# Battery.net
KiCad netlist of a schematic drawn in Altium Designer
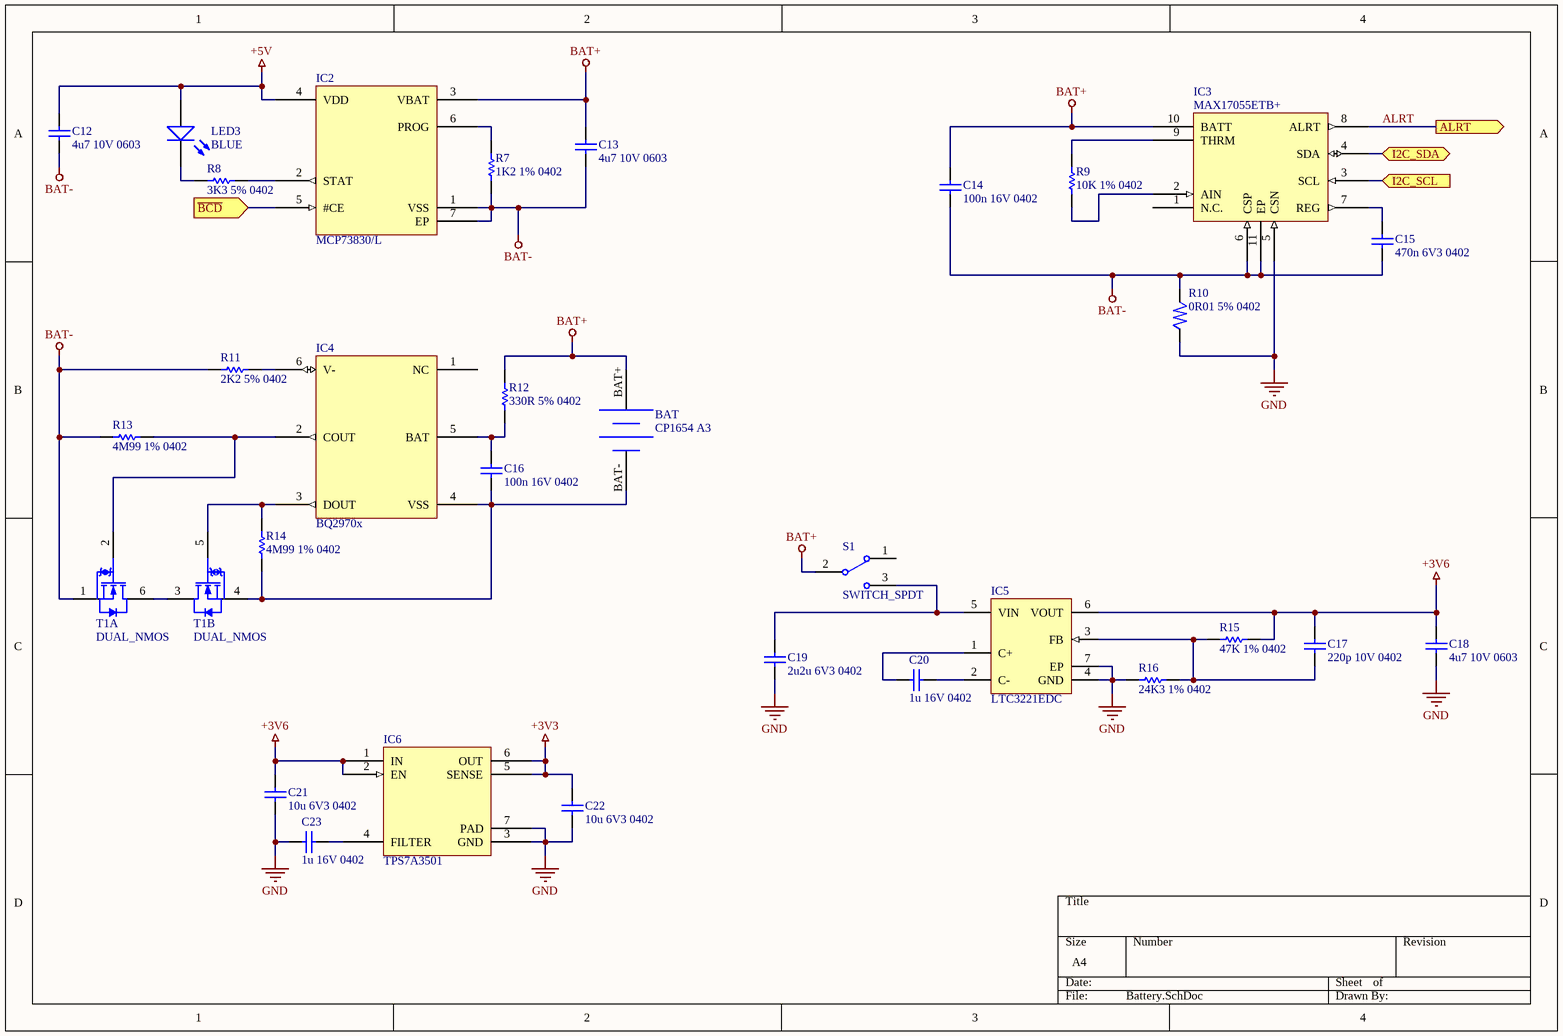
[diagram p0: Battery.SchDoc]

(export (version "E")
  (design (tool "Eeschema 10.0.6"))
  (components
    (comp (ref "BAT")
      (value "CP1654 A3")
      (footprint "CP1654")
      (libsource (lib "bleimuv6_intlib") (part "Battery"))
    )
    (comp (ref "C12")
      (value "4u7 10V 0603")
      (footprint "CAPC0603(1608)100_L")
      (description "CAP 4.7uF 10V ±20% 0603 (1608 Metric) Thickness 1mm SMD")
      (fields (field (name "TOLERANCE") "Â±20%"))
      (libsource (lib "Altium Content Vault") (part "CAP"))
    )
    (comp (ref "C13")
      (value "4u7 10V 0603")
      (footprint "CAPC0603(1608)100_L")
      (description "CAP 4.7uF 10V ±20% 0603 (1608 Metric) Thickness 1mm SMD")
      (fields (field (name "TOLERANCE") "Â±20%"))
      (libsource (lib "Altium Content Vault") (part "CAP"))
    )
    (comp (ref "C14")
      (value "100n 16V 0402")
      (footprint "CAPC0402(1005)60_L")
      (description "CAP 100nF 16V ±10% 0402 (1005 Metric) Thickness 0.6mm SMD")
      (fields (field (name "TOLERANCE") "Â±10%"))
      (libsource (lib "Altium Content Vault") (part "CAP"))
    )
    (comp (ref "C15")
      (value "470n 6V3 0402")
      (footprint "CAPC0402(1005)60_L")
      (description "CAP 470nF 6.3V ±10% 0402 (1005 Metric) Thickness 0.6mm SMD")
      (fields (field (name "TOLERANCE") "Â±10%"))
      (libsource (lib "Altium Content Vault") (part "CAP"))
    )
    (comp (ref "C16")
      (value "100n 16V 0402")
      (footprint "CAPC0402(1005)60_L")
      (description "CAP 100nF 16V ±10% 0402 (1005 Metric) Thickness 0.6mm SMD")
      (fields (field (name "TOLERANCE") "Â±10%"))
      (libsource (lib "Altium Content Vault") (part "CAP"))
    )
    (comp (ref "C17")
      (value "220p 10V 0402")
      (footprint "CAPC0402(1005)60_L")
      (description "CAP 220pF 10V ±5% 0402 (1005 Metric) Thickness 0.6mm SMD")
      (fields (field (name "TOLERANCE") "Â±5%"))
      (libsource (lib "Altium Content Vault") (part "CAP"))
    )
    (comp (ref "C18")
      (value "4u7 10V 0603")
      (footprint "CAPC0603(1608)100_L")
      (description "CAP 4.7uF 10V ±20% 0603 (1608 Metric) Thickness 1mm SMD")
      (fields (field (name "TOLERANCE") "Â±20%"))
      (libsource (lib "Altium Content Vault") (part "CAP"))
    )
    (comp (ref "C19")
      (value "2u2u 6V3 0402")
      (footprint "CAPC0402(1005)60_L")
      (description "CAP 2.2uF 6.3V ±10% 0402 (1005 Metric) Thickness 0.6mm SMD")
      (fields (field (name "TOLERANCE") "Â±10%"))
      (libsource (lib "Altium Content Vault") (part "CAP"))
    )
    (comp (ref "C20")
      (value "1u 16V 0402")
      (footprint "CAPC0402(1005)60_L")
      (description "CAP 1uF 16V ±10% 0402 (1005 Metric) Thickness 0.6mm SMD")
      (fields (field (name "TOLERANCE") "Â±10%"))
      (libsource (lib "Altium Content Vault") (part "CAP"))
    )
    (comp (ref "C21")
      (value "10u 6V3 0402")
      (footprint "CAPC0402(1005)60_L")
      (description "CAP 10uF 6.3V ±20% 0402 (1005 Metric) Thickness 0.6mm SMD")
      (fields (field (name "TOLERANCE") "Â±20%"))
      (libsource (lib "Altium Content Vault") (part "CAP"))
    )
    (comp (ref "C22")
      (value "10u 6V3 0402")
      (footprint "CAPC0402(1005)60_L")
      (description "CAP 10uF 6.3V ±20% 0402 (1005 Metric) Thickness 0.6mm SMD")
      (fields (field (name "TOLERANCE") "Â±20%"))
      (libsource (lib "Altium Content Vault") (part "CAP"))
    )
    (comp (ref "C23")
      (value "1u 16V 0402")
      (footprint "CAPC0402(1005)60_L")
      (description "CAP 1uF 16V ±10% 0402 (1005 Metric) Thickness 0.6mm SMD")
      (fields (field (name "TOLERANCE") "Â±10%"))
      (libsource (lib "Altium Content Vault") (part "CAP"))
    )
    (comp (ref "IC2")
      (value "MCP73830/L")
      (footprint "PSON50P200X80_HS-7L")
      (libsource (lib "bleimuv6_intlib") (part "MCP73830/L"))
    )
    (comp (ref "IC3")
      (value "MAX17055ETB+")
      (footprint "PSON40P250X80_HS-11L")
      (libsource (lib "bleimuv6_intlib") (part "MAX17055ETB+"))
    )
    (comp (ref "IC4")
      (value "BQ2970x")
      (footprint "SON50P150X80-6L")
      (libsource (lib "bleimuv6_intlib") (part "BQ2970x"))
    )
    (comp (ref "IC5")
      (value "LTC3221EDC")
      (footprint "LT-DC6-6_V")
      (fields (field (name "MANUFACTURER") "Linear Technology"))
      (libsource (lib "Altium Content Vault") (part "LT-LTC3221-DC6-6_B"))
    )
    (comp (ref "IC6")
      (value "TPS7A3501")
      (footprint "PSON65P200X80_HS-7L")
      (libsource (lib "bleimuv6_intlib") (part "TPS7A3501"))
    )
    (comp (ref "LED3")
      (value "BLUE")
      (footprint "LED_0402")
      (description "Generic 0402 LED")
      (libsource (lib "bleimuv6_schlib") (part "LED"))
    )
    (comp (ref "R7")
      (value "1K2 1% 0402")
      (footprint "RESC0402(1005)_L")
      (description "1K2 0.063W 1% 0402 (1005 Metric)  SMD")
      (fields (field (name "POWER") "0.063 W") (field (name "TOLERANCE") "1 %"))
      (libsource (lib "Altium Content Vault") (part "RES"))
    )
    (comp (ref "R8")
      (value "3K3 5% 0402")
      (footprint "RESC0402(1005)_L")
      (description "3K3 0.063W 5% 0402 (1005 Metric)  SMD")
      (fields (field (name "POWER") "0.063 W") (field (name "TOLERANCE") "5 %"))
      (libsource (lib "Altium Content Vault") (part "RES"))
    )
    (comp (ref "R9")
      (value "10K 1% 0402")
      (footprint "RESC0402(1005)_L")
      (description "10K 0.063W 1% 0402 (1005 Metric)  SMD")
      (fields (field (name "TOLERANCE") "1 %") (field (name "POWER") "0.063 W"))
      (libsource (lib "Altium Content Vault") (part "RES"))
    )
    (comp (ref "R10")
      (value "0R01 5% 0402")
      (footprint "R0402")
      (libsource (lib "bleimuv6_intlib") (part "Resistor"))
    )
    (comp (ref "R11")
      (value "2K2 5% 0402")
      (footprint "RESC0402(1005)_L")
      (description "2K2 0.063W 5% 0402 (1005 Metric)  SMD")
      (fields (field (name "TOLERANCE") "5 %") (field (name "POWER") "0.063 W"))
      (libsource (lib "Altium Content Vault") (part "RES"))
    )
    (comp (ref "R12")
      (value "330R 5% 0402")
      (footprint "RESC0402(1005)_L")
      (description "330R 0.063W 5% 0402 (1005 Metric)  SMD")
      (fields (field (name "TOLERANCE") "5 %") (field (name "POWER") "0.063 W"))
      (libsource (lib "Altium Content Vault") (part "RES"))
    )
    (comp (ref "R13")
      (value "4M99 1% 0402")
      (footprint "RESC0402(1005)_L")
      (description "4M99 0.063W 1% 0402 (1005 Metric)  SMD")
      (fields (field (name "TOLERANCE") "1 %") (field (name "POWER") "0.063 W"))
      (libsource (lib "Altium Content Vault") (part "RES"))
    )
    (comp (ref "R14")
      (value "4M99 1% 0402")
      (footprint "RESC0402(1005)_L")
      (description "4M99 0.063W 1% 0402 (1005 Metric)  SMD")
      (fields (field (name "TOLERANCE") "1 %") (field (name "POWER") "0.063 W"))
      (libsource (lib "Altium Content Vault") (part "RES"))
    )
    (comp (ref "R15")
      (value "47K 1% 0402")
      (footprint "RESC0402(1005)_L")
      (description "47K 0.063W 1% 0402 (1005 Metric)  SMD")
      (fields (field (name "POWER") "0.063 W") (field (name "TOLERANCE") "1 %"))
      (libsource (lib "Altium Content Vault") (part "RES"))
    )
    (comp (ref "R16")
      (value "24K3 1% 0402")
      (footprint "RESC0402(1005)_L")
      (description "24K3 0.063W 1% 0402 (1005 Metric)  SMD")
      (fields (field (name "TOLERANCE") "1 %") (field (name "POWER") "0.063 W"))
      (libsource (lib "Altium Content Vault") (part "RES"))
    )
    (comp (ref "S1")
      (value "SWITCH_SPDT")
      (footprint "SSSS810701_MODIFIED")
      (libsource (lib "bleimuv6_intlib") (part "SWITCH_SPDT"))
    )
    (comp (ref "T1")
      (value "DUAL_NMOS")
      (footprint "WDFN6 2x2, 0.65P")
      (libsource (lib "bleimuv6_intlib") (part "DUAL_NMOS"))
    )
  )
  (nets
    (net (code "1") (name "+3V3") (class "Default")
      (node (ref "C22") (pin "2") (pinfunction "2_2") (pintype "passive"))
      (node (ref "IC6") (pin "5") (pinfunction "SENSE_5") (pintype "power_in"))
      (node (ref "IC6") (pin "6") (pinfunction "OUT_6") (pintype "power_in"))
    )
    (net (code "2") (name "+3V6") (class "Default")
      (node (ref "C17") (pin "2") (pinfunction "2_2") (pintype "passive"))
      (node (ref "C18") (pin "2") (pinfunction "2_2") (pintype "passive"))
      (node (ref "C21") (pin "2") (pinfunction "2_2") (pintype "passive"))
      (node (ref "IC5") (pin "6") (pinfunction "VOUT_6") (pintype "power_in"))
      (node (ref "IC6") (pin "1") (pinfunction "IN_1") (pintype "power_in"))
      (node (ref "IC6") (pin "2") (pinfunction "EN_2") (pintype "input"))
      (node (ref "R15") (pin "2") (pinfunction "2_2") (pintype "passive"))
    )
    (net (code "3") (name "+5V") (class "Default")
      (node (ref "C12") (pin "2") (pinfunction "2_2") (pintype "passive"))
      (node (ref "IC2") (pin "4") (pinfunction "VDD_4") (pintype "power_in"))
      (node (ref "LED3") (pin "ANODE") (pinfunction "ANODE_ANODE") (pintype "passive"))
    )
    (net (code "4") (name "/ALRT") (class "Default")
      (node (ref "IC3") (pin "8") (pinfunction "ALRT_8") (pintype "output"))
    )
    (net (code "5") (name "/BCD") (class "Default")
      (node (ref "IC2") (pin "5") (pinfunction "#CE_5") (pintype "input"))
    )
    (net (code "6") (name "/I2C_SCL") (class "Default")
      (node (ref "IC3") (pin "3") (pinfunction "SCL_3") (pintype "input"))
    )
    (net (code "7") (name "/I2C_SDA") (class "Default")
      (node (ref "IC3") (pin "4") (pinfunction "SDA_4") (pintype "bidirectional"))
    )
    (net (code "8") (name "BAT+") (class "Default")
      (node (ref "BAT") (pin "BAT+") (pinfunction "BAT+_BAT+") (pintype "passive"))
      (node (ref "C13") (pin "2") (pinfunction "2_2") (pintype "passive"))
      (node (ref "C14") (pin "2") (pinfunction "2_2") (pintype "passive"))
      (node (ref "IC2") (pin "3") (pinfunction "VBAT_3") (pintype "power_in"))
      (node (ref "IC3") (pin "10") (pinfunction "BATT_10") (pintype "power_in"))
      (node (ref "R12") (pin "2") (pinfunction "2_2") (pintype "passive"))
      (node (ref "S1") (pin "2") (pinfunction "2_2") (pintype "passive"))
    )
    (net (code "9") (name "BAT-") (class "Default")
      (node (ref "C12") (pin "1") (pinfunction "1_1") (pintype "passive"))
      (node (ref "C13") (pin "1") (pinfunction "1_1") (pintype "passive"))
      (node (ref "C14") (pin "1") (pinfunction "1_1") (pintype "passive"))
      (node (ref "C15") (pin "1") (pinfunction "1_1") (pintype "passive"))
      (node (ref "IC2") (pin "1") (pinfunction "VSS_1") (pintype "power_in"))
      (node (ref "IC2") (pin "7") (pinfunction "EP_7") (pintype "power_in"))
      (node (ref "IC3") (pin "11") (pinfunction "EP_11") (pintype "power_in"))
      (node (ref "IC3") (pin "6") (pinfunction "CSP_6") (pintype "input"))
      (node (ref "R10") (pin "1") (pinfunction "24_1") (pintype "passive"))
      (node (ref "R11") (pin "1") (pinfunction "1_1") (pintype "passive"))
      (node (ref "R13") (pin "1") (pinfunction "1_1") (pintype "passive"))
      (node (ref "R7") (pin "1") (pinfunction "1_1") (pintype "passive"))
      (node (ref "T1") (pin "1") (pinfunction "S1_1") (pintype "passive"))
    )
    (net (code "10") (name "GND") (class "Default")
      (node (ref "C18") (pin "1") (pinfunction "1_1") (pintype "passive"))
      (node (ref "C19") (pin "1") (pinfunction "1_1") (pintype "passive"))
      (node (ref "C21") (pin "1") (pinfunction "1_1") (pintype "passive"))
      (node (ref "C22") (pin "1") (pinfunction "1_1") (pintype "passive"))
      (node (ref "C23") (pin "2") (pinfunction "2_2") (pintype "passive"))
      (node (ref "IC3") (pin "5") (pinfunction "CSN_5") (pintype "input"))
      (node (ref "IC5") (pin "4") (pinfunction "GND_4") (pintype "power_in"))
      (node (ref "IC5") (pin "7") (pinfunction "EP_7") (pintype "power_in"))
      (node (ref "IC6") (pin "3") (pinfunction "GND_3") (pintype "power_in"))
      (node (ref "IC6") (pin "7") (pinfunction "PAD_7") (pintype "power_in"))
      (node (ref "R10") (pin "2") (pinfunction "2_2") (pintype "passive"))
      (node (ref "R16") (pin "1") (pinfunction "1_1") (pintype "passive"))
    )
    (net (code "11") (name "Net-(IC2-PROG)") (class "Default")
      (node (ref "IC2") (pin "6") (pinfunction "PROG_6") (pintype "passive"))
      (node (ref "R7") (pin "2") (pinfunction "2_2") (pintype "passive"))
    )
    (net (code "12") (name "Net-(IC2-STAT)") (class "Default")
      (node (ref "IC2") (pin "2") (pinfunction "STAT_2") (pintype "output"))
      (node (ref "R8") (pin "2") (pinfunction "2_2") (pintype "passive"))
    )
    (net (code "13") (name "Net-(IC3-AIN)") (class "Default")
      (node (ref "IC3") (pin "2") (pinfunction "AIN_2") (pintype "input"))
      (node (ref "R9") (pin "1") (pinfunction "1_1") (pintype "passive"))
    )
    (net (code "14") (name "Net-(IC3-REG)") (class "Default")
      (node (ref "C15") (pin "2") (pinfunction "2_2") (pintype "passive"))
      (node (ref "IC3") (pin "7") (pinfunction "REG_7") (pintype "output"))
    )
    (net (code "15") (name "Net-(IC3-THRM)") (class "Default")
      (node (ref "IC3") (pin "9") (pinfunction "THRM_9") (pintype "passive"))
      (node (ref "R9") (pin "2") (pinfunction "2_2") (pintype "passive"))
    )
    (net (code "16") (name "Net-(IC4-BAT)") (class "Default")
      (node (ref "C16") (pin "2") (pinfunction "2_2") (pintype "passive"))
      (node (ref "IC4") (pin "5") (pinfunction "BAT_5") (pintype "power_in"))
      (node (ref "R12") (pin "1") (pinfunction "1_1") (pintype "passive"))
    )
    (net (code "17") (name "Net-(IC4-COUT)") (class "Default")
      (node (ref "IC4") (pin "2") (pinfunction "COUT_2") (pintype "output"))
      (node (ref "R13") (pin "2") (pinfunction "2_2") (pintype "passive"))
      (node (ref "T1") (pin "2") (pinfunction "G1_2") (pintype "passive"))
    )
    (net (code "18") (name "Net-(IC4-DOUT)") (class "Default")
      (node (ref "IC4") (pin "3") (pinfunction "DOUT_3") (pintype "output"))
      (node (ref "R14") (pin "2") (pinfunction "2_2") (pintype "passive"))
      (node (ref "T1") (pin "5") (pinfunction "G2_5") (pintype "passive"))
    )
    (net (code "19") (name "Net-(IC4-V-)") (class "Default")
      (node (ref "IC4") (pin "6") (pinfunction "V-_6") (pintype "bidirectional"))
      (node (ref "R11") (pin "2") (pinfunction "2_2") (pintype "passive"))
    )
    (net (code "20") (name "Net-(IC4-VSS)") (class "Default")
      (node (ref "BAT") (pin "BAT-") (pinfunction "BAT-_BAT-") (pintype "passive"))
      (node (ref "C16") (pin "1") (pinfunction "1_1") (pintype "passive"))
      (node (ref "IC4") (pin "4") (pinfunction "VSS_4") (pintype "power_in"))
      (node (ref "R14") (pin "1") (pinfunction "1_1") (pintype "passive"))
      (node (ref "T1") (pin "4") (pinfunction "S2_4") (pintype "passive"))
    )
    (net (code "21") (name "Net-(IC5-C+)") (class "Default")
      (node (ref "C20") (pin "2") (pinfunction "2_2") (pintype "passive"))
      (node (ref "IC5") (pin "1") (pinfunction "C+_1") (pintype "passive"))
    )
    (net (code "22") (name "Net-(IC5-C-)") (class "Default")
      (node (ref "C20") (pin "1") (pinfunction "1_1") (pintype "passive"))
      (node (ref "IC5") (pin "2") (pinfunction "C-_2") (pintype "passive"))
    )
    (net (code "23") (name "Net-(IC5-FB)") (class "Default")
      (node (ref "C17") (pin "1") (pinfunction "1_1") (pintype "passive"))
      (node (ref "IC5") (pin "3") (pinfunction "FB_3") (pintype "input"))
      (node (ref "R15") (pin "1") (pinfunction "1_1") (pintype "passive"))
      (node (ref "R16") (pin "2") (pinfunction "2_2") (pintype "passive"))
    )
    (net (code "24") (name "Net-(IC5-VIN)") (class "Default")
      (node (ref "C19") (pin "2") (pinfunction "2_2") (pintype "passive"))
      (node (ref "IC5") (pin "5") (pinfunction "VIN_5") (pintype "power_in"))
      (node (ref "S1") (pin "3") (pinfunction "3_3") (pintype "passive"))
    )
    (net (code "25") (name "Net-(IC6-FILTER)") (class "Default")
      (node (ref "C23") (pin "1") (pinfunction "1_1") (pintype "passive"))
      (node (ref "IC6") (pin "4") (pinfunction "FILTER_4") (pintype "passive"))
    )
    (net (code "26") (name "Net-(LED3-PadCATHODE)") (class "Default")
      (node (ref "LED3") (pin "CATHODE") (pinfunction "CATHODE_CATHODE") (pintype "passive"))
      (node (ref "R8") (pin "1") (pinfunction "1_1") (pintype "passive"))
    )
    (net (code "27") (name "Net-(T1A-D1)") (class "Default")
      (node (ref "T1") (pin "3") (pinfunction "D2_3") (pintype "passive"))
      (node (ref "T1") (pin "6") (pinfunction "D1_6") (pintype "passive"))
    )
    (net (code "28") (name "unconnected-(IC3-N.C.-Pad1)") (class "Default")
      (node (ref "IC3") (pin "1") (pinfunction "N.C._1") (pintype "passive"))
    )
    (net (code "29") (name "unconnected-(IC4-NC-Pad1)") (class "Default")
      (node (ref "IC4") (pin "1") (pinfunction "NC_1") (pintype "passive"))
    )
    (net (code "30") (name "unconnected-(S1-2-Pad1)") (class "Default")
      (node (ref "S1") (pin "1") (pinfunction "2_1") (pintype "passive"))
    )
  )
)
